# easyDRO_final.net
KiCad netlist of a schematic drawn in EAGLE
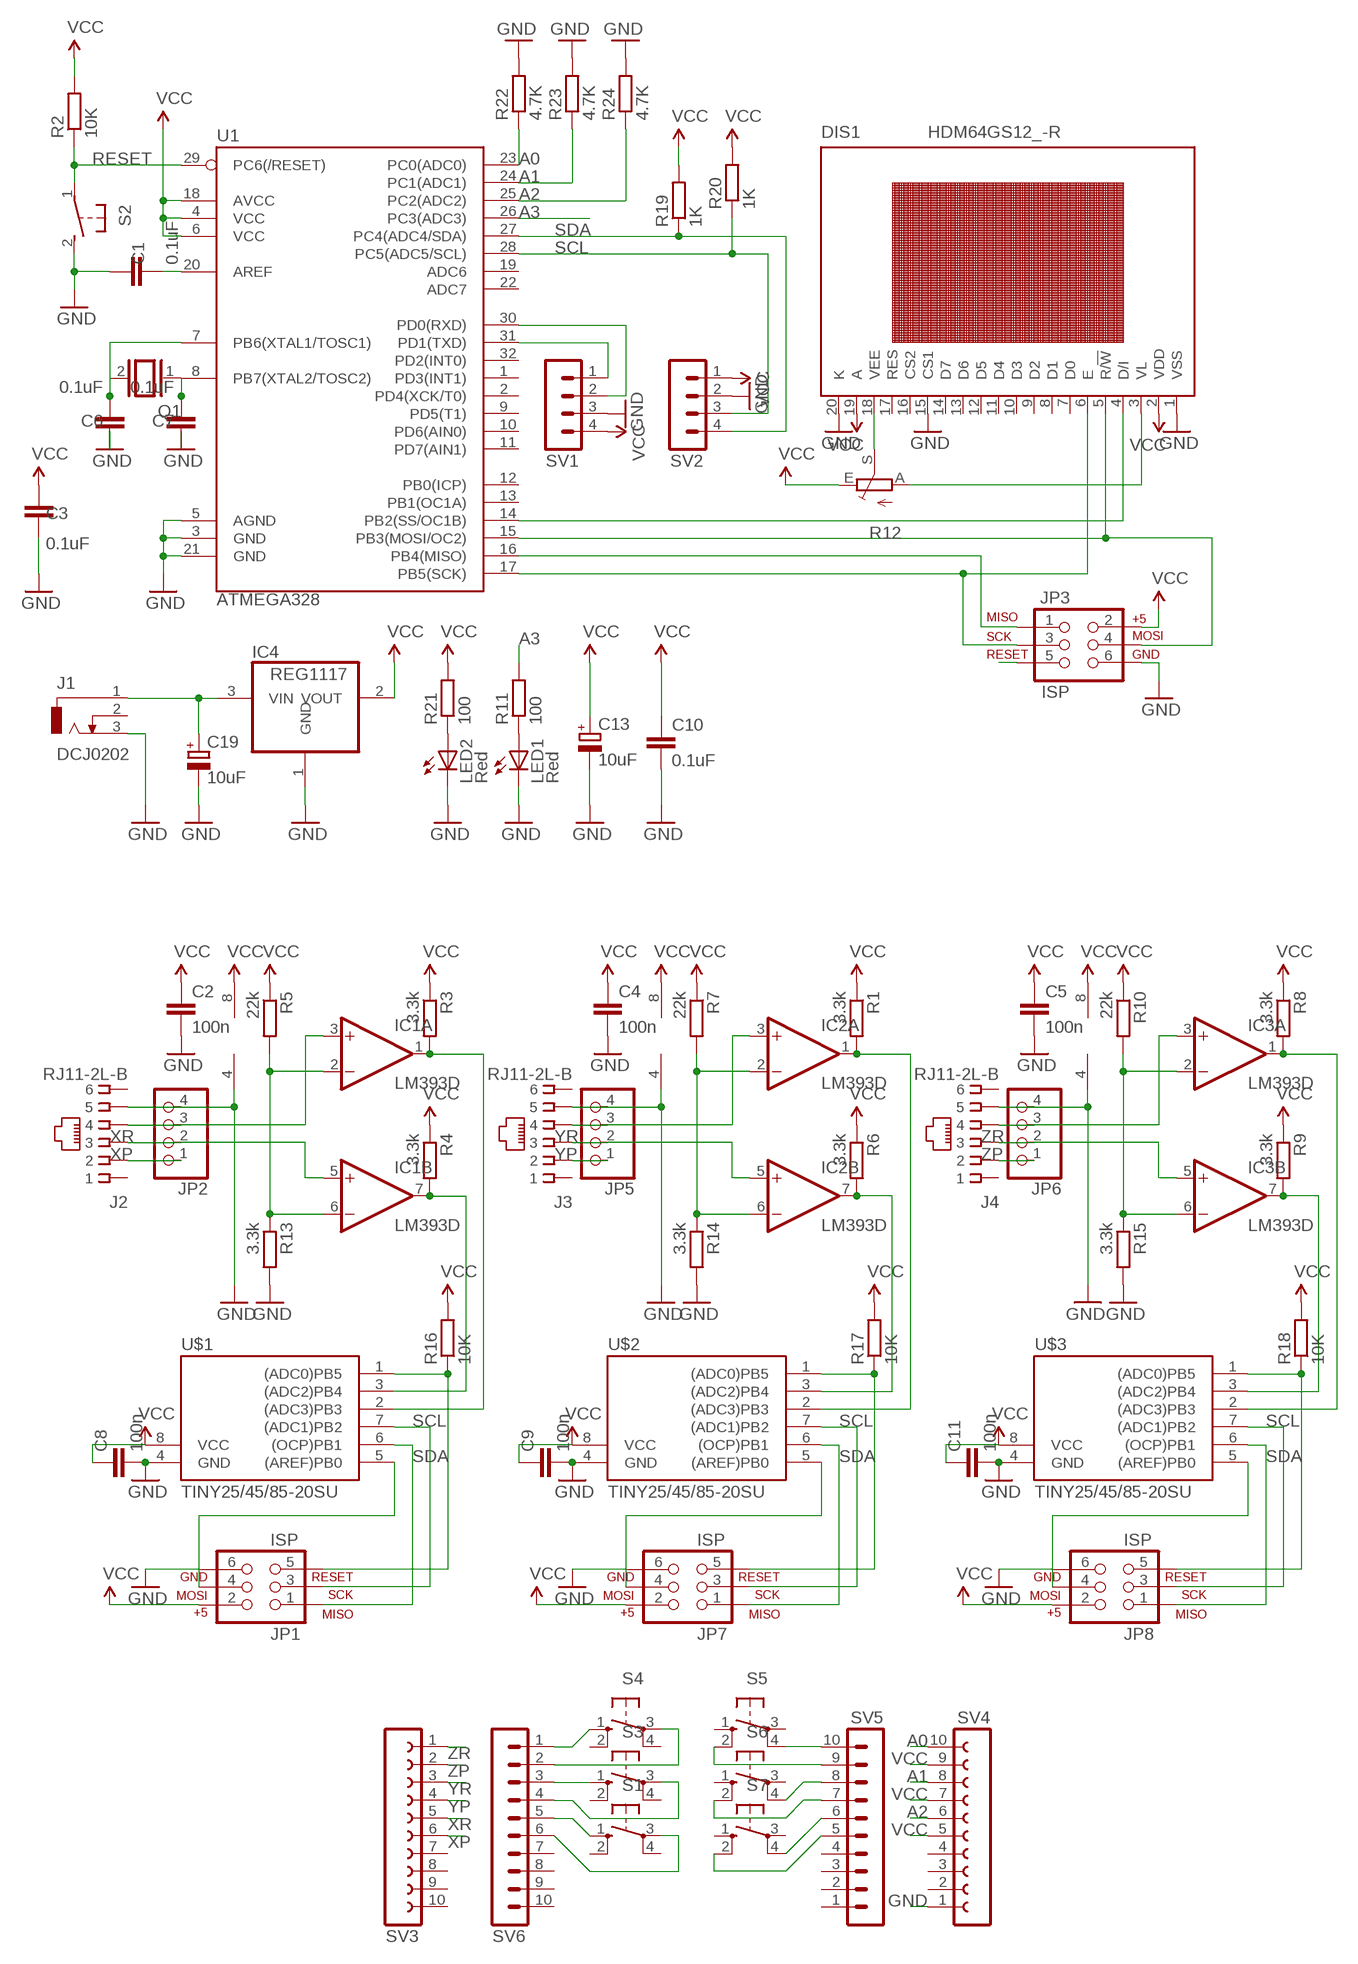
[diagram p0: schematic, sheet 1]

(export (version "E")
  (design (tool "Eeschema 10.0.6"))
  (components
    (comp (ref "C1")
      (value "0.1uF")
      (footprint "eagle-import:C0805")
      (libsource (lib "eagle-import") (part "resistor_C-EUC0805"))
    )
    (comp (ref "C2")
      (value "100n")
      (footprint "eagle-import:C0805")
      (libsource (lib "eagle-import") (part "resistor_C-EUC0805"))
    )
    (comp (ref "C3")
      (value "0.1uF")
      (footprint "eagle-import:C0805")
      (libsource (lib "eagle-import") (part "resistor_C-EUC0805"))
    )
    (comp (ref "C4")
      (value "100n")
      (footprint "eagle-import:C0805")
      (libsource (lib "eagle-import") (part "resistor_C-EUC0805"))
    )
    (comp (ref "C5")
      (value "100n")
      (footprint "eagle-import:C0805")
      (libsource (lib "eagle-import") (part "resistor_C-EUC0805"))
    )
    (comp (ref "C6")
      (value "0.1uF")
      (footprint "eagle-import:C0805")
      (libsource (lib "eagle-import") (part "resistor_C-EUC0805"))
    )
    (comp (ref "C7")
      (value "0.1uF")
      (footprint "eagle-import:C0805")
      (libsource (lib "eagle-import") (part "resistor_C-EUC0805"))
    )
    (comp (ref "C8")
      (value "100n")
      (footprint "eagle-import:C0805")
      (libsource (lib "eagle-import") (part "resistor_C-EUC0805"))
    )
    (comp (ref "C9")
      (value "100n")
      (footprint "eagle-import:C0805")
      (libsource (lib "eagle-import") (part "resistor_C-EUC0805"))
    )
    (comp (ref "C10")
      (value "0.1uF")
      (footprint "eagle-import:C0805")
      (libsource (lib "eagle-import") (part "C-EUC0805"))
    )
    (comp (ref "C11")
      (value "100n")
      (footprint "eagle-import:C0805")
      (libsource (lib "eagle-import") (part "resistor_C-EUC0805"))
    )
    (comp (ref "C13")
      (value "10uF")
      (footprint "eagle-import:E2,5-5")
      (libsource (lib "eagle-import") (part "CPOL-EUE2.5-5"))
    )
    (comp (ref "C19")
      (value "10uF")
      (footprint "eagle-import:E2,5-5")
      (libsource (lib "eagle-import") (part "CPOL-EUE2.5-5"))
    )
    (comp (ref "DIS1")
      (value "HDM64GS12_-R")
      (footprint "eagle-import:HDM64GS12_-R")
      (libsource (lib "eagle-import") (part "HDM64GS12_-R"))
    )
    (comp (ref "IC1")
      (value "LM393D")
      (footprint "eagle-import:SO08")
      (libsource (lib "eagle-import") (part "LM393D"))
    )
    (comp (ref "IC2")
      (value "LM393D")
      (footprint "eagle-import:SO08")
      (libsource (lib "eagle-import") (part "LM393D"))
    )
    (comp (ref "IC3")
      (value "LM393D")
      (footprint "eagle-import:SO08")
      (libsource (lib "eagle-import") (part "LM393D"))
    )
    (comp (ref "IC4")
      (value "REG1117")
      (footprint "eagle-import:SOT223")
      (libsource (lib "eagle-import") (part "REG1117"))
    )
    (comp (ref "J1")
      (value "DCJ0202")
      (footprint "eagle-import:DCJ0202")
      (libsource (lib "eagle-import") (part "DCJ0202"))
    )
    (comp (ref "J2")
      (value "RJ11-2L-B")
      (footprint "eagle-import:RJ11-NO_SHIELD")
      (fields (field (name "MF") "TYCO ELECTRONICS"))
      (libsource (lib "eagle-import") (part "RJ11-2L-B"))
    )
    (comp (ref "J3")
      (value "RJ11-2L-B")
      (footprint "eagle-import:RJ11-NO_SHIELD")
      (fields (field (name "MF") "TYCO ELECTRONICS"))
      (libsource (lib "eagle-import") (part "RJ11-2L-B"))
    )
    (comp (ref "J4")
      (value "RJ11-2L-B")
      (footprint "eagle-import:RJ11-NO_SHIELD")
      (fields (field (name "MF") "TYCO ELECTRONICS"))
      (libsource (lib "eagle-import") (part "RJ11-2L-B"))
    )
    (comp (ref "JP1")
      (value "ISP")
      (footprint "eagle-import:2X3")
      (libsource (lib "eagle-import") (part "AVR_SPI_PRG_6PTH"))
    )
    (comp (ref "JP2")
      (value "PINHD-1X4/90")
      (footprint "eagle-import:1X04_90")
      (libsource (lib "eagle-import") (part "PINHD-1X4/90"))
    )
    (comp (ref "JP3")
      (value "ISP")
      (footprint "eagle-import:2X3")
      (libsource (lib "eagle-import") (part "AVR_SPI_PRG_6PTH"))
    )
    (comp (ref "JP5")
      (value "PINHD-1X4/90")
      (footprint "eagle-import:1X04_90")
      (libsource (lib "eagle-import") (part "PINHD-1X4/90"))
    )
    (comp (ref "JP6")
      (value "PINHD-1X4/90")
      (footprint "eagle-import:1X04_90")
      (libsource (lib "eagle-import") (part "PINHD-1X4/90"))
    )
    (comp (ref "JP7")
      (value "ISP")
      (footprint "eagle-import:2X3")
      (libsource (lib "eagle-import") (part "AVR_SPI_PRG_6PTH"))
    )
    (comp (ref "JP8")
      (value "ISP")
      (footprint "eagle-import:2X3")
      (libsource (lib "eagle-import") (part "AVR_SPI_PRG_6PTH"))
    )
    (comp (ref "LED1")
      (value "Red")
      (footprint "eagle-import:LED5MM")
      (libsource (lib "eagle-import") (part "LED5MM"))
    )
    (comp (ref "LED2")
      (value "Red")
      (footprint "eagle-import:LED5MM")
      (libsource (lib "eagle-import") (part "LED5MM"))
    )
    (comp (ref "Q1")
      (value "XTAL/S")
      (footprint "eagle-import:QS")
      (libsource (lib "eagle-import") (part "XTAL/S"))
    )
    (comp (ref "R1")
      (value "3.3k")
      (footprint "eagle-import:R0805")
      (libsource (lib "eagle-import") (part "resistor_R-EU_R0805"))
    )
    (comp (ref "R2")
      (value "10K")
      (footprint "eagle-import:R0805")
      (libsource (lib "eagle-import") (part "resistor_R-EU_R0805"))
    )
    (comp (ref "R3")
      (value "3.3k")
      (footprint "eagle-import:R0805")
      (libsource (lib "eagle-import") (part "resistor_R-EU_R0805"))
    )
    (comp (ref "R4")
      (value "3.3k")
      (footprint "eagle-import:R0805")
      (libsource (lib "eagle-import") (part "resistor_R-EU_R0805"))
    )
    (comp (ref "R5")
      (value "22k")
      (footprint "eagle-import:R0805")
      (libsource (lib "eagle-import") (part "resistor_R-EU_R0805"))
    )
    (comp (ref "R6")
      (value "3.3k")
      (footprint "eagle-import:R0805")
      (libsource (lib "eagle-import") (part "resistor_R-EU_R0805"))
    )
    (comp (ref "R7")
      (value "22k")
      (footprint "eagle-import:R0805")
      (libsource (lib "eagle-import") (part "resistor_R-EU_R0805"))
    )
    (comp (ref "R8")
      (value "3.3k")
      (footprint "eagle-import:R0805")
      (libsource (lib "eagle-import") (part "resistor_R-EU_R0805"))
    )
    (comp (ref "R9")
      (value "3.3k")
      (footprint "eagle-import:R0805")
      (libsource (lib "eagle-import") (part "resistor_R-EU_R0805"))
    )
    (comp (ref "R10")
      (value "22k")
      (footprint "eagle-import:R0805")
      (libsource (lib "eagle-import") (part "resistor_R-EU_R0805"))
    )
    (comp (ref "R11")
      (value "100")
      (footprint "eagle-import:R0805")
      (libsource (lib "eagle-import") (part "resistor_R-EU_R0805"))
    )
    (comp (ref "R12")
      (value "TRIM_EU-CA6H")
      (footprint "eagle-import:CA6H")
      (libsource (lib "eagle-import") (part "TRIM_EU-CA6H"))
    )
    (comp (ref "R13")
      (value "3.3k")
      (footprint "eagle-import:R0805")
      (libsource (lib "eagle-import") (part "R-EU_R0805"))
    )
    (comp (ref "R14")
      (value "3.3k")
      (footprint "eagle-import:R0805")
      (libsource (lib "eagle-import") (part "resistor_R-EU_R0805"))
    )
    (comp (ref "R15")
      (value "3.3k")
      (footprint "eagle-import:R0805")
      (libsource (lib "eagle-import") (part "resistor_R-EU_R0805"))
    )
    (comp (ref "R16")
      (value "10K")
      (footprint "eagle-import:R0805")
      (libsource (lib "eagle-import") (part "resistor_R-EU_R0805"))
    )
    (comp (ref "R17")
      (value "10K")
      (footprint "eagle-import:R0805")
      (libsource (lib "eagle-import") (part "resistor_R-EU_R0805"))
    )
    (comp (ref "R18")
      (value "10K")
      (footprint "eagle-import:R0805")
      (libsource (lib "eagle-import") (part "resistor_R-EU_R0805"))
    )
    (comp (ref "R19")
      (value "1K")
      (footprint "eagle-import:R0805")
      (libsource (lib "eagle-import") (part "resistor_R-EU_R0805"))
    )
    (comp (ref "R20")
      (value "1K")
      (footprint "eagle-import:R0805")
      (libsource (lib "eagle-import") (part "resistor_R-EU_R0805"))
    )
    (comp (ref "R21")
      (value "100")
      (footprint "eagle-import:R0805")
      (libsource (lib "eagle-import") (part "resistor_R-EU_R0805"))
    )
    (comp (ref "R22")
      (value "4.7K")
      (footprint "eagle-import:R0805")
      (libsource (lib "eagle-import") (part "resistor_R-EU_R0805"))
    )
    (comp (ref "R23")
      (value "4.7K")
      (footprint "eagle-import:R0805")
      (libsource (lib "eagle-import") (part "resistor_R-EU_R0805"))
    )
    (comp (ref "R24")
      (value "4.7K")
      (footprint "eagle-import:R0805")
      (libsource (lib "eagle-import") (part "resistor_R-EU_R0805"))
    )
    (comp (ref "S1")
      (value "40-XX")
      (footprint "eagle-import:B3F-40XX")
      (fields (field (name "MF") "OMRON COMPONENTS USA") (field (name "MPN") "B3F-4000"))
      (libsource (lib "eagle-import") (part "40-XX"))
    )
    (comp (ref "S2")
      (value "31-XX")
      (footprint "eagle-import:B3F-31XX")
      (fields (field (name "MPN") "B3F-3100"))
      (libsource (lib "eagle-import") (part "31-XX"))
    )
    (comp (ref "S3")
      (value "40-XX")
      (footprint "eagle-import:B3F-40XX")
      (fields (field (name "MF") "OMRON COMPONENTS USA") (field (name "MPN") "B3F-4000"))
      (libsource (lib "eagle-import") (part "40-XX"))
    )
    (comp (ref "S4")
      (value "40-XX")
      (footprint "eagle-import:B3F-40XX")
      (fields (field (name "MF") "OMRON COMPONENTS USA") (field (name "MPN") "B3F-4000"))
      (libsource (lib "eagle-import") (part "40-XX"))
    )
    (comp (ref "S5")
      (value "40-XX")
      (footprint "eagle-import:B3F-40XX")
      (fields (field (name "MF") "OMRON COMPONENTS USA") (field (name "MPN") "B3F-4000"))
      (libsource (lib "eagle-import") (part "40-XX"))
    )
    (comp (ref "S6")
      (value "40-XX")
      (footprint "eagle-import:B3F-40XX")
      (fields (field (name "MF") "OMRON COMPONENTS USA") (field (name "MPN") "B3F-4000"))
      (libsource (lib "eagle-import") (part "40-XX"))
    )
    (comp (ref "S7")
      (value "40-XX")
      (footprint "eagle-import:B3F-40XX")
      (fields (field (name "MF") "OMRON COMPONENTS USA") (field (name "MPN") "B3F-4000"))
      (libsource (lib "eagle-import") (part "40-XX"))
    )
    (comp (ref "SV1")
      (value "MA04-1")
      (footprint "eagle-import:MA04-1")
      (libsource (lib "eagle-import") (part "MA04-1"))
    )
    (comp (ref "SV2")
      (value "MA04-1")
      (footprint "eagle-import:MA04-1")
      (libsource (lib "eagle-import") (part "MA04-1"))
    )
    (comp (ref "SV3")
      (value "FE10-1")
      (footprint "eagle-import:FE10")
      (libsource (lib "eagle-import") (part "FE10-1"))
    )
    (comp (ref "SV4")
      (value "FE10-1")
      (footprint "eagle-import:FE10")
      (libsource (lib "eagle-import") (part "FE10-1"))
    )
    (comp (ref "SV5")
      (value "MA10-1")
      (footprint "eagle-import:MA10-1")
      (libsource (lib "eagle-import") (part "MA10-1"))
    )
    (comp (ref "SV6")
      (value "MA10-1")
      (footprint "eagle-import:MA10-1")
      (libsource (lib "eagle-import") (part "MA10-1"))
    )
    (comp (ref "U$1")
      (value "TINY25/45/85-20SU")
      (footprint "eagle-import:SOIC8")
      (libsource (lib "eagle-import") (part "TINY25/45/85-20SU"))
    )
    (comp (ref "U$2")
      (value "TINY25/45/85-20SU")
      (footprint "eagle-import:SOIC8")
      (libsource (lib "eagle-import") (part "TINY25/45/85-20SU"))
    )
    (comp (ref "U$3")
      (value "TINY25/45/85-20SU")
      (footprint "eagle-import:SOIC8")
      (libsource (lib "eagle-import") (part "TINY25/45/85-20SU"))
    )
    (comp (ref "U1")
      (value "ATMEGA328")
      (footprint "eagle-import:TQFP32-08")
      (libsource (lib "eagle-import") (part "ATMEGA168"))
    )
  )
  (nets
    (net (code "1") (name "/A0") (class "Default")
      (node (ref "R22") (pin "1") (pinfunction "1_1") (pintype "passive"))
      (node (ref "SV4") (pin "10") (pinfunction "10_10") (pintype "passive"))
      (node (ref "U1") (pin "23") (pinfunction "PC0(ADC0)_23") (pintype "bidirectional"))
    )
    (net (code "2") (name "/A1") (class "Default")
      (node (ref "R23") (pin "1") (pinfunction "1_1") (pintype "passive"))
      (node (ref "SV4") (pin "8") (pinfunction "8_8") (pintype "passive"))
      (node (ref "U1") (pin "24") (pinfunction "PC1(ADC1)_24") (pintype "bidirectional"))
    )
    (net (code "3") (name "/A2") (class "Default")
      (node (ref "R24") (pin "1") (pinfunction "1_1") (pintype "passive"))
      (node (ref "SV4") (pin "6") (pinfunction "6_6") (pintype "passive"))
      (node (ref "U1") (pin "25") (pinfunction "PC2(ADC2)_25") (pintype "bidirectional"))
    )
    (net (code "4") (name "/A3") (class "Default")
      (node (ref "R11") (pin "2") (pinfunction "2_2") (pintype "passive"))
      (node (ref "U1") (pin "26") (pinfunction "PC3(ADC3)_26") (pintype "bidirectional"))
    )
    (net (code "5") (name "/RESET") (class "Default")
      (node (ref "JP3") (pin "5") (pinfunction "5_5") (pintype "passive"))
      (node (ref "R2") (pin "1") (pinfunction "1_1") (pintype "passive"))
      (node (ref "S2") (pin "1") (pinfunction "P_1") (pintype "passive"))
      (node (ref "U1") (pin "29") (pinfunction "PC6(/RESET)_29") (pintype "bidirectional"))
    )
    (net (code "6") (name "/SCL") (class "Default")
      (node (ref "JP1") (pin "3") (pinfunction "3_3") (pintype "passive"))
      (node (ref "JP7") (pin "3") (pinfunction "3_3") (pintype "passive"))
      (node (ref "JP8") (pin "3") (pinfunction "3_3") (pintype "passive"))
      (node (ref "R20") (pin "1") (pinfunction "1_1") (pintype "passive"))
      (node (ref "SV2") (pin "3") (pinfunction "3_3") (pintype "passive"))
      (node (ref "U$1") (pin "7") (pinfunction "(ADC1)PB2_7") (pintype "bidirectional"))
      (node (ref "U$2") (pin "7") (pinfunction "(ADC1)PB2_7") (pintype "bidirectional"))
      (node (ref "U$3") (pin "7") (pinfunction "(ADC1)PB2_7") (pintype "bidirectional"))
      (node (ref "U1") (pin "28") (pinfunction "PC5(ADC5/SCL)_28") (pintype "bidirectional"))
    )
    (net (code "7") (name "/SDA") (class "Default")
      (node (ref "JP1") (pin "4") (pinfunction "4_4") (pintype "passive"))
      (node (ref "JP7") (pin "4") (pinfunction "4_4") (pintype "passive"))
      (node (ref "JP8") (pin "4") (pinfunction "4_4") (pintype "passive"))
      (node (ref "R19") (pin "1") (pinfunction "1_1") (pintype "passive"))
      (node (ref "SV2") (pin "4") (pinfunction "4_4") (pintype "passive"))
      (node (ref "U$1") (pin "5") (pinfunction "(AREF)PB0_5") (pintype "bidirectional"))
      (node (ref "U$2") (pin "5") (pinfunction "(AREF)PB0_5") (pintype "bidirectional"))
      (node (ref "U$3") (pin "5") (pinfunction "(AREF)PB0_5") (pintype "bidirectional"))
      (node (ref "U1") (pin "27") (pinfunction "PC4(ADC4/SDA)_27") (pintype "bidirectional"))
    )
    (net (code "8") (name "/XP") (class "Default")
      (node (ref "J2") (pin "2") (pinfunction "2_2") (pintype "passive"))
      (node (ref "JP2") (pin "1") (pinfunction "1_1") (pintype "passive"))
      (node (ref "SV3") (pin "6") (pinfunction "6_6") (pintype "passive"))
    )
    (net (code "9") (name "/XR") (class "Default")
      (node (ref "IC1") (pin "5") (pinfunction "+IN_5") (pintype "input"))
      (node (ref "J2") (pin "3") (pinfunction "3_3") (pintype "passive"))
      (node (ref "JP2") (pin "2") (pinfunction "2_2") (pintype "passive"))
      (node (ref "SV3") (pin "5") (pinfunction "5_5") (pintype "passive"))
    )
    (net (code "10") (name "/YP") (class "Default")
      (node (ref "J3") (pin "2") (pinfunction "2_2") (pintype "passive"))
      (node (ref "JP5") (pin "1") (pinfunction "1_1") (pintype "passive"))
      (node (ref "SV3") (pin "4") (pinfunction "4_4") (pintype "passive"))
    )
    (net (code "11") (name "/YR") (class "Default")
      (node (ref "IC2") (pin "5") (pinfunction "+IN_5") (pintype "input"))
      (node (ref "J3") (pin "3") (pinfunction "3_3") (pintype "passive"))
      (node (ref "JP5") (pin "2") (pinfunction "2_2") (pintype "passive"))
      (node (ref "SV3") (pin "3") (pinfunction "3_3") (pintype "passive"))
    )
    (net (code "12") (name "/ZP") (class "Default")
      (node (ref "J4") (pin "2") (pinfunction "2_2") (pintype "passive"))
      (node (ref "JP6") (pin "1") (pinfunction "1_1") (pintype "passive"))
      (node (ref "SV3") (pin "2") (pinfunction "2_2") (pintype "passive"))
    )
    (net (code "13") (name "/ZR") (class "Default")
      (node (ref "IC3") (pin "5") (pinfunction "+IN_5") (pintype "input"))
      (node (ref "J4") (pin "3") (pinfunction "3_3") (pintype "passive"))
      (node (ref "JP6") (pin "2") (pinfunction "2_2") (pintype "passive"))
      (node (ref "SV3") (pin "1") (pinfunction "1_1") (pintype "passive"))
    )
    (net (code "14") (name "GND") (class "Default")
      (node (ref "C1") (pin "2") (pinfunction "2_2") (pintype "passive"))
      (node (ref "C10") (pin "2") (pinfunction "2_2") (pintype "passive"))
      (node (ref "C11") (pin "2") (pinfunction "2_2") (pintype "passive"))
      (node (ref "C13") (pin "-") (pinfunction "-_-") (pintype "passive"))
      (node (ref "C19") (pin "-") (pinfunction "-_-") (pintype "passive"))
      (node (ref "C2") (pin "2") (pinfunction "2_2") (pintype "passive"))
      (node (ref "C3") (pin "1") (pinfunction "1_1") (pintype "passive"))
      (node (ref "C4") (pin "2") (pinfunction "2_2") (pintype "passive"))
      (node (ref "C5") (pin "2") (pinfunction "2_2") (pintype "passive"))
      (node (ref "C6") (pin "2") (pinfunction "2_2") (pintype "passive"))
      (node (ref "C7") (pin "2") (pinfunction "2_2") (pintype "passive"))
      (node (ref "C8") (pin "2") (pinfunction "2_2") (pintype "passive"))
      (node (ref "C9") (pin "2") (pinfunction "2_2") (pintype "passive"))
      (node (ref "DIS1") (pin "1") (pinfunction "VSS_1") (pintype "power_in"))
      (node (ref "DIS1") (pin "15") (pinfunction "CS1_15") (pintype "input"))
      (node (ref "DIS1") (pin "20") (pinfunction "K_20") (pintype "passive"))
      (node (ref "IC1") (pin "4") (pinfunction "V-_4") (pintype "power_in"))
      (node (ref "IC2") (pin "4") (pinfunction "V-_4") (pintype "power_in"))
      (node (ref "IC3") (pin "4") (pinfunction "V-_4") (pintype "power_in"))
      (node (ref "IC4") (pin "1") (pinfunction "GND_1") (pintype "power_in"))
      (node (ref "J1") (pin "3") (pinfunction "3_3") (pintype "passive"))
      (node (ref "J2") (pin "5") (pinfunction "5_5") (pintype "passive"))
      (node (ref "J3") (pin "5") (pinfunction "5_5") (pintype "passive"))
      (node (ref "J4") (pin "5") (pinfunction "5_5") (pintype "passive"))
      (node (ref "JP1") (pin "6") (pinfunction "6_6") (pintype "passive"))
      (node (ref "JP2") (pin "4") (pinfunction "4_4") (pintype "passive"))
      (node (ref "JP3") (pin "6") (pinfunction "6_6") (pintype "passive"))
      (node (ref "JP5") (pin "4") (pinfunction "4_4") (pintype "passive"))
      (node (ref "JP6") (pin "4") (pinfunction "4_4") (pintype "passive"))
      (node (ref "JP7") (pin "6") (pinfunction "6_6") (pintype "passive"))
      (node (ref "JP8") (pin "6") (pinfunction "6_6") (pintype "passive"))
      (node (ref "LED1") (pin "K") (pinfunction "C_K") (pintype "passive"))
      (node (ref "LED2") (pin "K") (pinfunction "C_K") (pintype "passive"))
      (node (ref "R13") (pin "2") (pinfunction "2_2") (pintype "passive"))
      (node (ref "R14") (pin "2") (pinfunction "2_2") (pintype "passive"))
      (node (ref "R15") (pin "2") (pinfunction "2_2") (pintype "passive"))
      (node (ref "R22") (pin "2") (pinfunction "2_2") (pintype "passive"))
      (node (ref "R23") (pin "2") (pinfunction "2_2") (pintype "passive"))
      (node (ref "R24") (pin "2") (pinfunction "2_2") (pintype "passive"))
      (node (ref "S2") (pin "2") (pinfunction "S_2") (pintype "passive"))
      (node (ref "SV1") (pin "3") (pinfunction "3_3") (pintype "passive"))
      (node (ref "SV2") (pin "2") (pinfunction "2_2") (pintype "passive"))
      (node (ref "SV4") (pin "1") (pinfunction "1_1") (pintype "passive"))
      (node (ref "U$1") (pin "4") (pinfunction "GND_4") (pintype "power_in"))
      (node (ref "U$2") (pin "4") (pinfunction "GND_4") (pintype "power_in"))
      (node (ref "U$3") (pin "4") (pinfunction "GND_4") (pintype "power_in"))
      (node (ref "U1") (pin "21") (pinfunction "GND_21") (pintype "bidirectional"))
      (node (ref "U1") (pin "3") (pinfunction "GND_3") (pintype "bidirectional"))
      (node (ref "U1") (pin "5") (pinfunction "AGND_5") (pintype "bidirectional"))
    )
    (net (code "15") (name "Net-(DIS1-D{slash}I)") (class "Default")
      (node (ref "DIS1") (pin "4") (pinfunction "D/I_4") (pintype "input"))
      (node (ref "U1") (pin "14") (pinfunction "PB2(SS/OC1B)_14") (pintype "bidirectional"))
    )
    (net (code "16") (name "Net-(DIS1-E)") (class "Default")
      (node (ref "DIS1") (pin "6") (pinfunction "E_6") (pintype "input"))
      (node (ref "JP3") (pin "3") (pinfunction "3_3") (pintype "passive"))
      (node (ref "U1") (pin "17") (pinfunction "PB5(SCK)_17") (pintype "bidirectional"))
    )
    (net (code "17") (name "Net-(DIS1-R{slash}~{W})") (class "Default")
      (node (ref "DIS1") (pin "5") (pinfunction "R/~{W}_5") (pintype "input"))
      (node (ref "JP3") (pin "4") (pinfunction "4_4") (pintype "passive"))
      (node (ref "U1") (pin "15") (pinfunction "PB3(MOSI/OC2)_15") (pintype "bidirectional"))
    )
    (net (code "18") (name "Net-(DIS1-VEE)") (class "Default")
      (node (ref "DIS1") (pin "18") (pinfunction "VEE_18") (pintype "output"))
      (node (ref "R12") (pin "S") (pinfunction "S_S") (pintype "passive"))
    )
    (net (code "19") (name "Net-(DIS1-VL)") (class "Default")
      (node (ref "DIS1") (pin "3") (pinfunction "VL_3") (pintype "passive"))
      (node (ref "R12") (pin "A") (pinfunction "A_A") (pintype "passive"))
    )
    (net (code "20") (name "Net-(IC1A-+IN)") (class "Default")
      (node (ref "IC1") (pin "3") (pinfunction "+IN_3") (pintype "input"))
      (node (ref "J2") (pin "4") (pinfunction "4_4") (pintype "passive"))
      (node (ref "JP2") (pin "3") (pinfunction "3_3") (pintype "passive"))
    )
    (net (code "21") (name "Net-(IC1A--IN)") (class "Default")
      (node (ref "IC1") (pin "2") (pinfunction "-IN_2") (pintype "input"))
      (node (ref "IC1") (pin "6") (pinfunction "-IN_6") (pintype "input"))
      (node (ref "R13") (pin "1") (pinfunction "1_1") (pintype "passive"))
      (node (ref "R5") (pin "2") (pinfunction "2_2") (pintype "passive"))
    )
    (net (code "22") (name "Net-(IC1A-OUT)") (class "Default")
      (node (ref "IC1") (pin "1") (pinfunction "OUT_1") (pintype "output"))
      (node (ref "R3") (pin "2") (pinfunction "2_2") (pintype "passive"))
      (node (ref "U$1") (pin "2") (pinfunction "(ADC3)PB3_2") (pintype "bidirectional"))
    )
    (net (code "23") (name "Net-(IC1B-OUT)") (class "Default")
      (node (ref "IC1") (pin "7") (pinfunction "OUT_7") (pintype "output"))
      (node (ref "R4") (pin "2") (pinfunction "2_2") (pintype "passive"))
      (node (ref "U$1") (pin "3") (pinfunction "(ADC2)PB4_3") (pintype "bidirectional"))
    )
    (net (code "24") (name "Net-(IC2A-+IN)") (class "Default")
      (node (ref "IC2") (pin "3") (pinfunction "+IN_3") (pintype "input"))
      (node (ref "J3") (pin "4") (pinfunction "4_4") (pintype "passive"))
      (node (ref "JP5") (pin "3") (pinfunction "3_3") (pintype "passive"))
    )
    (net (code "25") (name "Net-(IC2A--IN)") (class "Default")
      (node (ref "IC2") (pin "2") (pinfunction "-IN_2") (pintype "input"))
      (node (ref "IC2") (pin "6") (pinfunction "-IN_6") (pintype "input"))
      (node (ref "R14") (pin "1") (pinfunction "1_1") (pintype "passive"))
      (node (ref "R7") (pin "2") (pinfunction "2_2") (pintype "passive"))
    )
    (net (code "26") (name "Net-(IC2A-OUT)") (class "Default")
      (node (ref "IC2") (pin "1") (pinfunction "OUT_1") (pintype "output"))
      (node (ref "R1") (pin "2") (pinfunction "2_2") (pintype "passive"))
      (node (ref "U$2") (pin "2") (pinfunction "(ADC3)PB3_2") (pintype "bidirectional"))
    )
    (net (code "27") (name "Net-(IC2B-OUT)") (class "Default")
      (node (ref "IC2") (pin "7") (pinfunction "OUT_7") (pintype "output"))
      (node (ref "R6") (pin "2") (pinfunction "2_2") (pintype "passive"))
      (node (ref "U$2") (pin "3") (pinfunction "(ADC2)PB4_3") (pintype "bidirectional"))
    )
    (net (code "28") (name "Net-(IC3A-+IN)") (class "Default")
      (node (ref "IC3") (pin "3") (pinfunction "+IN_3") (pintype "input"))
      (node (ref "J4") (pin "4") (pinfunction "4_4") (pintype "passive"))
      (node (ref "JP6") (pin "3") (pinfunction "3_3") (pintype "passive"))
    )
    (net (code "29") (name "Net-(IC3A--IN)") (class "Default")
      (node (ref "IC3") (pin "2") (pinfunction "-IN_2") (pintype "input"))
      (node (ref "IC3") (pin "6") (pinfunction "-IN_6") (pintype "input"))
      (node (ref "R10") (pin "2") (pinfunction "2_2") (pintype "passive"))
      (node (ref "R15") (pin "1") (pinfunction "1_1") (pintype "passive"))
    )
    (net (code "30") (name "Net-(IC3A-OUT)") (class "Default")
      (node (ref "IC3") (pin "1") (pinfunction "OUT_1") (pintype "output"))
      (node (ref "R8") (pin "2") (pinfunction "2_2") (pintype "passive"))
      (node (ref "U$3") (pin "2") (pinfunction "(ADC3)PB3_2") (pintype "bidirectional"))
    )
    (net (code "31") (name "Net-(IC3B-OUT)") (class "Default")
      (node (ref "IC3") (pin "7") (pinfunction "OUT_7") (pintype "output"))
      (node (ref "R9") (pin "2") (pinfunction "2_2") (pintype "passive"))
      (node (ref "U$3") (pin "3") (pinfunction "(ADC2)PB4_3") (pintype "bidirectional"))
    )
    (net (code "32") (name "Net-(IC4-VIN)") (class "Default")
      (node (ref "C19") (pin "+") (pinfunction "+_+") (pintype "passive"))
      (node (ref "IC4") (pin "3") (pinfunction "VIN_3") (pintype "input"))
      (node (ref "J1") (pin "1") (pinfunction "1_1") (pintype "passive"))
    )
    (net (code "33") (name "Net-(LED1-PadA)") (class "Default")
      (node (ref "LED1") (pin "A") (pinfunction "A_A") (pintype "passive"))
      (node (ref "R11") (pin "1") (pinfunction "1_1") (pintype "passive"))
    )
    (net (code "34") (name "Net-(LED2-PadA)") (class "Default")
      (node (ref "LED2") (pin "A") (pinfunction "A_A") (pintype "passive"))
      (node (ref "R21") (pin "1") (pinfunction "1_1") (pintype "passive"))
    )
    (net (code "35") (name "Net-(S1-P)") (class "Default")
      (node (ref "S1") (pin "3") (pinfunction "P_3") (pintype "passive"))
      (node (ref "SV6") (pin "6") (pinfunction "6_6") (pintype "passive"))
    )
    (net (code "36") (name "Net-(S1-S)") (class "Default")
      (node (ref "S1") (pin "1") (pinfunction "S_1") (pintype "passive"))
      (node (ref "SV6") (pin "5") (pinfunction "5_5") (pintype "passive"))
    )
    (net (code "37") (name "Net-(S3-P)") (class "Default")
      (node (ref "S3") (pin "3") (pinfunction "P_3") (pintype "passive"))
      (node (ref "SV6") (pin "4") (pinfunction "4_4") (pintype "passive"))
    )
    (net (code "38") (name "Net-(S3-S)") (class "Default")
      (node (ref "S3") (pin "1") (pinfunction "S_1") (pintype "passive"))
      (node (ref "SV6") (pin "3") (pinfunction "3_3") (pintype "passive"))
    )
    (net (code "39") (name "Net-(S4-P)") (class "Default")
      (node (ref "S4") (pin "3") (pinfunction "P_3") (pintype "passive"))
      (node (ref "SV6") (pin "2") (pinfunction "2_2") (pintype "passive"))
    )
    (net (code "40") (name "Net-(S4-S)") (class "Default")
      (node (ref "S4") (pin "1") (pinfunction "S_1") (pintype "passive"))
      (node (ref "SV6") (pin "1") (pinfunction "1_1") (pintype "passive"))
    )
    (net (code "41") (name "Net-(S5-P1)") (class "Default")
      (node (ref "S5") (pin "4") (pinfunction "P1_4") (pintype "passive"))
      (node (ref "SV5") (pin "10") (pinfunction "10_10") (pintype "passive"))
    )
    (net (code "42") (name "Net-(S5-S1)") (class "Default")
      (node (ref "S5") (pin "2") (pinfunction "S1_2") (pintype "passive"))
      (node (ref "SV5") (pin "9") (pinfunction "9_9") (pintype "passive"))
    )
    (net (code "43") (name "Net-(S6-P1)") (class "Default")
      (node (ref "S6") (pin "4") (pinfunction "P1_4") (pintype "passive"))
      (node (ref "SV5") (pin "8") (pinfunction "8_8") (pintype "passive"))
    )
    (net (code "44") (name "Net-(S6-S1)") (class "Default")
      (node (ref "S6") (pin "2") (pinfunction "S1_2") (pintype "passive"))
      (node (ref "SV5") (pin "7") (pinfunction "7_7") (pintype "passive"))
    )
    (net (code "45") (name "Net-(S7-P1)") (class "Default")
      (node (ref "S7") (pin "4") (pinfunction "P1_4") (pintype "passive"))
      (node (ref "SV5") (pin "6") (pinfunction "6_6") (pintype "passive"))
    )
    (net (code "46") (name "Net-(S7-S1)") (class "Default")
      (node (ref "S7") (pin "2") (pinfunction "S1_2") (pintype "passive"))
      (node (ref "SV5") (pin "5") (pinfunction "5_5") (pintype "passive"))
    )
    (net (code "47") (name "Net-(U$1-(ADC0)PB5)") (class "Default")
      (node (ref "JP1") (pin "5") (pinfunction "5_5") (pintype "passive"))
      (node (ref "R16") (pin "1") (pinfunction "1_1") (pintype "passive"))
      (node (ref "U$1") (pin "1") (pinfunction "(ADC0)PB5_1") (pintype "bidirectional"))
    )
    (net (code "48") (name "Net-(U$1-(OCP)PB1)") (class "Default")
      (node (ref "JP1") (pin "1") (pinfunction "1_1") (pintype "passive"))
      (node (ref "U$1") (pin "6") (pinfunction "(OCP)PB1_6") (pintype "bidirectional"))
    )
    (net (code "49") (name "Net-(U$2-(ADC0)PB5)") (class "Default")
      (node (ref "JP7") (pin "5") (pinfunction "5_5") (pintype "passive"))
      (node (ref "R17") (pin "1") (pinfunction "1_1") (pintype "passive"))
      (node (ref "U$2") (pin "1") (pinfunction "(ADC0)PB5_1") (pintype "bidirectional"))
    )
    (net (code "50") (name "Net-(U$2-(OCP)PB1)") (class "Default")
      (node (ref "JP7") (pin "1") (pinfunction "1_1") (pintype "passive"))
      (node (ref "U$2") (pin "6") (pinfunction "(OCP)PB1_6") (pintype "bidirectional"))
    )
    (net (code "51") (name "Net-(U$3-(ADC0)PB5)") (class "Default")
      (node (ref "JP8") (pin "5") (pinfunction "5_5") (pintype "passive"))
      (node (ref "R18") (pin "1") (pinfunction "1_1") (pintype "passive"))
      (node (ref "U$3") (pin "1") (pinfunction "(ADC0)PB5_1") (pintype "bidirectional"))
    )
    (net (code "52") (name "Net-(U$3-(OCP)PB1)") (class "Default")
      (node (ref "JP8") (pin "1") (pinfunction "1_1") (pintype "passive"))
      (node (ref "U$3") (pin "6") (pinfunction "(OCP)PB1_6") (pintype "bidirectional"))
    )
    (net (code "53") (name "Net-(U1-AREF)") (class "Default")
      (node (ref "C1") (pin "1") (pinfunction "1_1") (pintype "passive"))
      (node (ref "U1") (pin "20") (pinfunction "AREF_20") (pintype "bidirectional"))
    )
    (net (code "54") (name "Net-(U1-PB4(MISO))") (class "Default")
      (node (ref "JP3") (pin "1") (pinfunction "1_1") (pintype "passive"))
      (node (ref "U1") (pin "16") (pinfunction "PB4(MISO)_16") (pintype "bidirectional"))
    )
    (net (code "55") (name "Net-(U1-PB6(XTAL1{slash}TOSC1))") (class "Default")
      (node (ref "C6") (pin "1") (pinfunction "1_1") (pintype "passive"))
      (node (ref "Q1") (pin "2") (pinfunction "2_2") (pintype "passive"))
      (node (ref "U1") (pin "7") (pinfunction "PB6(XTAL1/TOSC1)_7") (pintype "bidirectional"))
    )
    (net (code "56") (name "Net-(U1-PB7(XTAL2{slash}TOSC2))") (class "Default")
      (node (ref "C7") (pin "1") (pinfunction "1_1") (pintype "passive"))
      (node (ref "Q1") (pin "1") (pinfunction "1_1") (pintype "passive"))
      (node (ref "U1") (pin "8") (pinfunction "PB7(XTAL2/TOSC2)_8") (pintype "bidirectional"))
    )
    (net (code "57") (name "Net-(U1-PD0(RXD))") (class "Default")
      (node (ref "SV1") (pin "2") (pinfunction "2_2") (pintype "passive"))
      (node (ref "U1") (pin "30") (pinfunction "PD0(RXD)_30") (pintype "bidirectional"))
    )
    (net (code "58") (name "Net-(U1-PD1(TXD))") (class "Default")
      (node (ref "SV1") (pin "1") (pinfunction "1_1") (pintype "passive"))
      (node (ref "U1") (pin "31") (pinfunction "PD1(TXD)_31") (pintype "bidirectional"))
    )
    (net (code "59") (name "VCC") (class "Default")
      (node (ref "C10") (pin "1") (pinfunction "1_1") (pintype "passive"))
      (node (ref "C11") (pin "1") (pinfunction "1_1") (pintype "passive"))
      (node (ref "C13") (pin "+") (pinfunction "+_+") (pintype "passive"))
      (node (ref "C2") (pin "1") (pinfunction "1_1") (pintype "passive"))
      (node (ref "C3") (pin "2") (pinfunction "2_2") (pintype "passive"))
      (node (ref "C4") (pin "1") (pinfunction "1_1") (pintype "passive"))
      (node (ref "C5") (pin "1") (pinfunction "1_1") (pintype "passive"))
      (node (ref "C8") (pin "1") (pinfunction "1_1") (pintype "passive"))
      (node (ref "C9") (pin "1") (pinfunction "1_1") (pintype "passive"))
      (node (ref "DIS1") (pin "19") (pinfunction "A_19") (pintype "passive"))
      (node (ref "DIS1") (pin "2") (pinfunction "VDD_2") (pintype "power_in"))
      (node (ref "IC1") (pin "8") (pinfunction "V+_8") (pintype "power_in"))
      (node (ref "IC2") (pin "8") (pinfunction "V+_8") (pintype "power_in"))
      (node (ref "IC3") (pin "8") (pinfunction "V+_8") (pintype "power_in"))
      (node (ref "IC4") (pin "2") (pinfunction "VOUT_2") (pintype "output"))
      (node (ref "JP1") (pin "2") (pinfunction "2_2") (pintype "passive"))
      (node (ref "JP3") (pin "2") (pinfunction "2_2") (pintype "passive"))
      (node (ref "JP7") (pin "2") (pinfunction "2_2") (pintype "passive"))
      (node (ref "JP8") (pin "2") (pinfunction "2_2") (pintype "passive"))
      (node (ref "R1") (pin "1") (pinfunction "1_1") (pintype "passive"))
      (node (ref "R10") (pin "1") (pinfunction "1_1") (pintype "passive"))
      (node (ref "R12") (pin "E") (pinfunction "E_E") (pintype "passive"))
      (node (ref "R16") (pin "2") (pinfunction "2_2") (pintype "passive"))
      (node (ref "R17") (pin "2") (pinfunction "2_2") (pintype "passive"))
      (node (ref "R18") (pin "2") (pinfunction "2_2") (pintype "passive"))
      (node (ref "R19") (pin "2") (pinfunction "2_2") (pintype "passive"))
      (node (ref "R2") (pin "2") (pinfunction "2_2") (pintype "passive"))
      (node (ref "R20") (pin "2") (pinfunction "2_2") (pintype "passive"))
      (node (ref "R21") (pin "2") (pinfunction "2_2") (pintype "passive"))
      (node (ref "R3") (pin "1") (pinfunction "1_1") (pintype "passive"))
      (node (ref "R4") (pin "1") (pinfunction "1_1") (pintype "passive"))
      (node (ref "R5") (pin "1") (pinfunction "1_1") (pintype "passive"))
      (node (ref "R6") (pin "1") (pinfunction "1_1") (pintype "passive"))
      (node (ref "R7") (pin "1") (pinfunction "1_1") (pintype "passive"))
      (node (ref "R8") (pin "1") (pinfunction "1_1") (pintype "passive"))
      (node (ref "R9") (pin "1") (pinfunction "1_1") (pintype "passive"))
      (node (ref "SV1") (pin "4") (pinfunction "4_4") (pintype "passive"))
      (node (ref "SV2") (pin "1") (pinfunction "1_1") (pintype "passive"))
      (node (ref "SV4") (pin "5") (pinfunction "5_5") (pintype "passive"))
      (node (ref "SV4") (pin "7") (pinfunction "7_7") (pintype "passive"))
      (node (ref "SV4") (pin "9") (pinfunction "9_9") (pintype "passive"))
      (node (ref "U$1") (pin "8") (pinfunction "VCC_8") (pintype "power_in"))
      (node (ref "U$2") (pin "8") (pinfunction "VCC_8") (pintype "power_in"))
      (node (ref "U$3") (pin "8") (pinfunction "VCC_8") (pintype "power_in"))
      (node (ref "U1") (pin "18") (pinfunction "AVCC_18") (pintype "bidirectional"))
      (node (ref "U1") (pin "4") (pinfunction "VCC_4") (pintype "bidirectional"))
      (node (ref "U1") (pin "6") (pinfunction "VCC_6") (pintype "bidirectional"))
    )
    (net (code "60") (name "unconnected-(DIS1-CS2-Pad16)") (class "Default")
      (node (ref "DIS1") (pin "16") (pinfunction "CS2_16") (pintype "input"))
    )
    (net (code "61") (name "unconnected-(DIS1-D0-Pad7)") (class "Default")
      (node (ref "DIS1") (pin "7") (pinfunction "D0_7") (pintype "bidirectional"))
    )
    (net (code "62") (name "unconnected-(DIS1-D1-Pad8)") (class "Default")
      (node (ref "DIS1") (pin "8") (pinfunction "D1_8") (pintype "bidirectional"))
    )
    (net (code "63") (name "unconnected-(DIS1-D2-Pad9)") (class "Default")
      (node (ref "DIS1") (pin "9") (pinfunction "D2_9") (pintype "bidirectional"))
    )
    (net (code "64") (name "unconnected-(DIS1-D3-Pad10)") (class "Default")
      (node (ref "DIS1") (pin "10") (pinfunction "D3_10") (pintype "bidirectional"))
    )
    (net (code "65") (name "unconnected-(DIS1-D4-Pad11)") (class "Default")
      (node (ref "DIS1") (pin "11") (pinfunction "D4_11") (pintype "bidirectional"))
    )
    (net (code "66") (name "unconnected-(DIS1-D5-Pad12)") (class "Default")
      (node (ref "DIS1") (pin "12") (pinfunction "D5_12") (pintype "bidirectional"))
    )
    (net (code "67") (name "unconnected-(DIS1-D6-Pad13)") (class "Default")
      (node (ref "DIS1") (pin "13") (pinfunction "D6_13") (pintype "bidirectional"))
    )
    (net (code "68") (name "unconnected-(DIS1-D7-Pad14)") (class "Default")
      (node (ref "DIS1") (pin "14") (pinfunction "D7_14") (pintype "bidirectional"))
    )
    (net (code "69") (name "unconnected-(DIS1-RES-Pad17)") (class "Default")
      (node (ref "DIS1") (pin "17") (pinfunction "RES_17") (pintype "input"))
    )
    (net (code "70") (name "unconnected-(J1-Pad2)") (class "Default")
      (node (ref "J1") (pin "2") (pinfunction "2_2") (pintype "passive"))
    )
    (net (code "71") (name "unconnected-(J2-Pad1)") (class "Default")
      (node (ref "J2") (pin "1") (pinfunction "1_1") (pintype "passive"))
    )
    (net (code "72") (name "unconnected-(J2-Pad6)") (class "Default")
      (node (ref "J2") (pin "6") (pinfunction "6_6") (pintype "passive"))
    )
    (net (code "73") (name "unconnected-(J3-Pad1)") (class "Default")
      (node (ref "J3") (pin "1") (pinfunction "1_1") (pintype "passive"))
    )
    (net (code "74") (name "unconnected-(J3-Pad6)") (class "Default")
      (node (ref "J3") (pin "6") (pinfunction "6_6") (pintype "passive"))
    )
    (net (code "75") (name "unconnected-(J4-Pad1)") (class "Default")
      (node (ref "J4") (pin "1") (pinfunction "1_1") (pintype "passive"))
    )
    (net (code "76") (name "unconnected-(J4-Pad6)") (class "Default")
      (node (ref "J4") (pin "6") (pinfunction "6_6") (pintype "passive"))
    )
    (net (code "77") (name "unconnected-(S1-P1-Pad4)") (class "Default")
      (node (ref "S1") (pin "4") (pinfunction "P1_4") (pintype "passive"))
    )
    (net (code "78") (name "unconnected-(S1-S1-Pad2)") (class "Default")
      (node (ref "S1") (pin "2") (pinfunction "S1_2") (pintype "passive"))
    )
    (net (code "79") (name "unconnected-(S3-P1-Pad4)") (class "Default")
      (node (ref "S3") (pin "4") (pinfunction "P1_4") (pintype "passive"))
    )
    (net (code "80") (name "unconnected-(S3-S1-Pad2)") (class "Default")
      (node (ref "S3") (pin "2") (pinfunction "S1_2") (pintype "passive"))
    )
    (net (code "81") (name "unconnected-(S4-P1-Pad4)") (class "Default")
      (node (ref "S4") (pin "4") (pinfunction "P1_4") (pintype "passive"))
    )
    (net (code "82") (name "unconnected-(S4-S1-Pad2)") (class "Default")
      (node (ref "S4") (pin "2") (pinfunction "S1_2") (pintype "passive"))
    )
    (net (code "83") (name "unconnected-(S5-P-Pad3)") (class "Default")
      (node (ref "S5") (pin "3") (pinfunction "P_3") (pintype "passive"))
    )
    (net (code "84") (name "unconnected-(S5-S-Pad1)") (class "Default")
      (node (ref "S5") (pin "1") (pinfunction "S_1") (pintype "passive"))
    )
    (net (code "85") (name "unconnected-(S6-P-Pad3)") (class "Default")
      (node (ref "S6") (pin "3") (pinfunction "P_3") (pintype "passive"))
    )
    (net (code "86") (name "unconnected-(S6-S-Pad1)") (class "Default")
      (node (ref "S6") (pin "1") (pinfunction "S_1") (pintype "passive"))
    )
    (net (code "87") (name "unconnected-(S7-P-Pad3)") (class "Default")
      (node (ref "S7") (pin "3") (pinfunction "P_3") (pintype "passive"))
    )
    (net (code "88") (name "unconnected-(S7-S-Pad1)") (class "Default")
      (node (ref "S7") (pin "1") (pinfunction "S_1") (pintype "passive"))
    )
    (net (code "89") (name "unconnected-(SV3-Pad7)") (class "Default")
      (node (ref "SV3") (pin "7") (pinfunction "7_7") (pintype "passive"))
    )
    (net (code "90") (name "unconnected-(SV3-Pad8)") (class "Default")
      (node (ref "SV3") (pin "8") (pinfunction "8_8") (pintype "passive"))
    )
    (net (code "91") (name "unconnected-(SV3-Pad9)") (class "Default")
      (node (ref "SV3") (pin "9") (pinfunction "9_9") (pintype "passive"))
    )
    (net (code "92") (name "unconnected-(SV3-Pad10)") (class "Default")
      (node (ref "SV3") (pin "10") (pinfunction "10_10") (pintype "passive"))
    )
    (net (code "93") (name "unconnected-(SV4-Pad2)") (class "Default")
      (node (ref "SV4") (pin "2") (pinfunction "2_2") (pintype "passive"))
    )
    (net (code "94") (name "unconnected-(SV4-Pad3)") (class "Default")
      (node (ref "SV4") (pin "3") (pinfunction "3_3") (pintype "passive"))
    )
    (net (code "95") (name "unconnected-(SV4-Pad4)") (class "Default")
      (node (ref "SV4") (pin "4") (pinfunction "4_4") (pintype "passive"))
    )
    (net (code "96") (name "unconnected-(SV5-Pad1)") (class "Default")
      (node (ref "SV5") (pin "1") (pinfunction "1_1") (pintype "passive"))
    )
    (net (code "97") (name "unconnected-(SV5-Pad2)") (class "Default")
      (node (ref "SV5") (pin "2") (pinfunction "2_2") (pintype "passive"))
    )
    (net (code "98") (name "unconnected-(SV5-Pad3)") (class "Default")
      (node (ref "SV5") (pin "3") (pinfunction "3_3") (pintype "passive"))
    )
    (net (code "99") (name "unconnected-(SV5-Pad4)") (class "Default")
      (node (ref "SV5") (pin "4") (pinfunction "4_4") (pintype "passive"))
    )
    (net (code "100") (name "unconnected-(SV6-Pad7)") (class "Default")
      (node (ref "SV6") (pin "7") (pinfunction "7_7") (pintype "passive"))
    )
    (net (code "101") (name "unconnected-(SV6-Pad8)") (class "Default")
      (node (ref "SV6") (pin "8") (pinfunction "8_8") (pintype "passive"))
    )
    (net (code "102") (name "unconnected-(SV6-Pad9)") (class "Default")
      (node (ref "SV6") (pin "9") (pinfunction "9_9") (pintype "passive"))
    )
    (net (code "103") (name "unconnected-(SV6-Pad10)") (class "Default")
      (node (ref "SV6") (pin "10") (pinfunction "10_10") (pintype "passive"))
    )
    (net (code "104") (name "unconnected-(U1-ADC6-Pad19)") (class "Default")
      (node (ref "U1") (pin "19") (pinfunction "ADC6_19") (pintype "bidirectional"))
    )
    (net (code "105") (name "unconnected-(U1-ADC7-Pad22)") (class "Default")
      (node (ref "U1") (pin "22") (pinfunction "ADC7_22") (pintype "bidirectional"))
    )
    (net (code "106") (name "unconnected-(U1-PB0(ICP)-Pad12)") (class "Default")
      (node (ref "U1") (pin "12") (pinfunction "PB0(ICP)_12") (pintype "bidirectional"))
    )
    (net (code "107") (name "unconnected-(U1-PB1(OC1A)-Pad13)") (class "Default")
      (node (ref "U1") (pin "13") (pinfunction "PB1(OC1A)_13") (pintype "bidirectional"))
    )
    (net (code "108") (name "unconnected-(U1-PD2(INT0)-Pad32)") (class "Default")
      (node (ref "U1") (pin "32") (pinfunction "PD2(INT0)_32") (pintype "bidirectional"))
    )
    (net (code "109") (name "unconnected-(U1-PD3(INT1)-Pad1)") (class "Default")
      (node (ref "U1") (pin "1") (pinfunction "PD3(INT1)_1") (pintype "bidirectional"))
    )
    (net (code "110") (name "unconnected-(U1-PD4(XCK{slash}T0)-Pad2)") (class "Default")
      (node (ref "U1") (pin "2") (pinfunction "PD4(XCK/T0)_2") (pintype "bidirectional"))
    )
    (net (code "111") (name "unconnected-(U1-PD5(T1)-Pad9)") (class "Default")
      (node (ref "U1") (pin "9") (pinfunction "PD5(T1)_9") (pintype "bidirectional"))
    )
    (net (code "112") (name "unconnected-(U1-PD6(AIN0)-Pad10)") (class "Default")
      (node (ref "U1") (pin "10") (pinfunction "PD6(AIN0)_10") (pintype "bidirectional"))
    )
    (net (code "113") (name "unconnected-(U1-PD7(AIN1)-Pad11)") (class "Default")
      (node (ref "U1") (pin "11") (pinfunction "PD7(AIN1)_11") (pintype "bidirectional"))
    )
  )
)
